# Proiect_v23.net
KiCad netlist of a schematic drawn in EAGLE
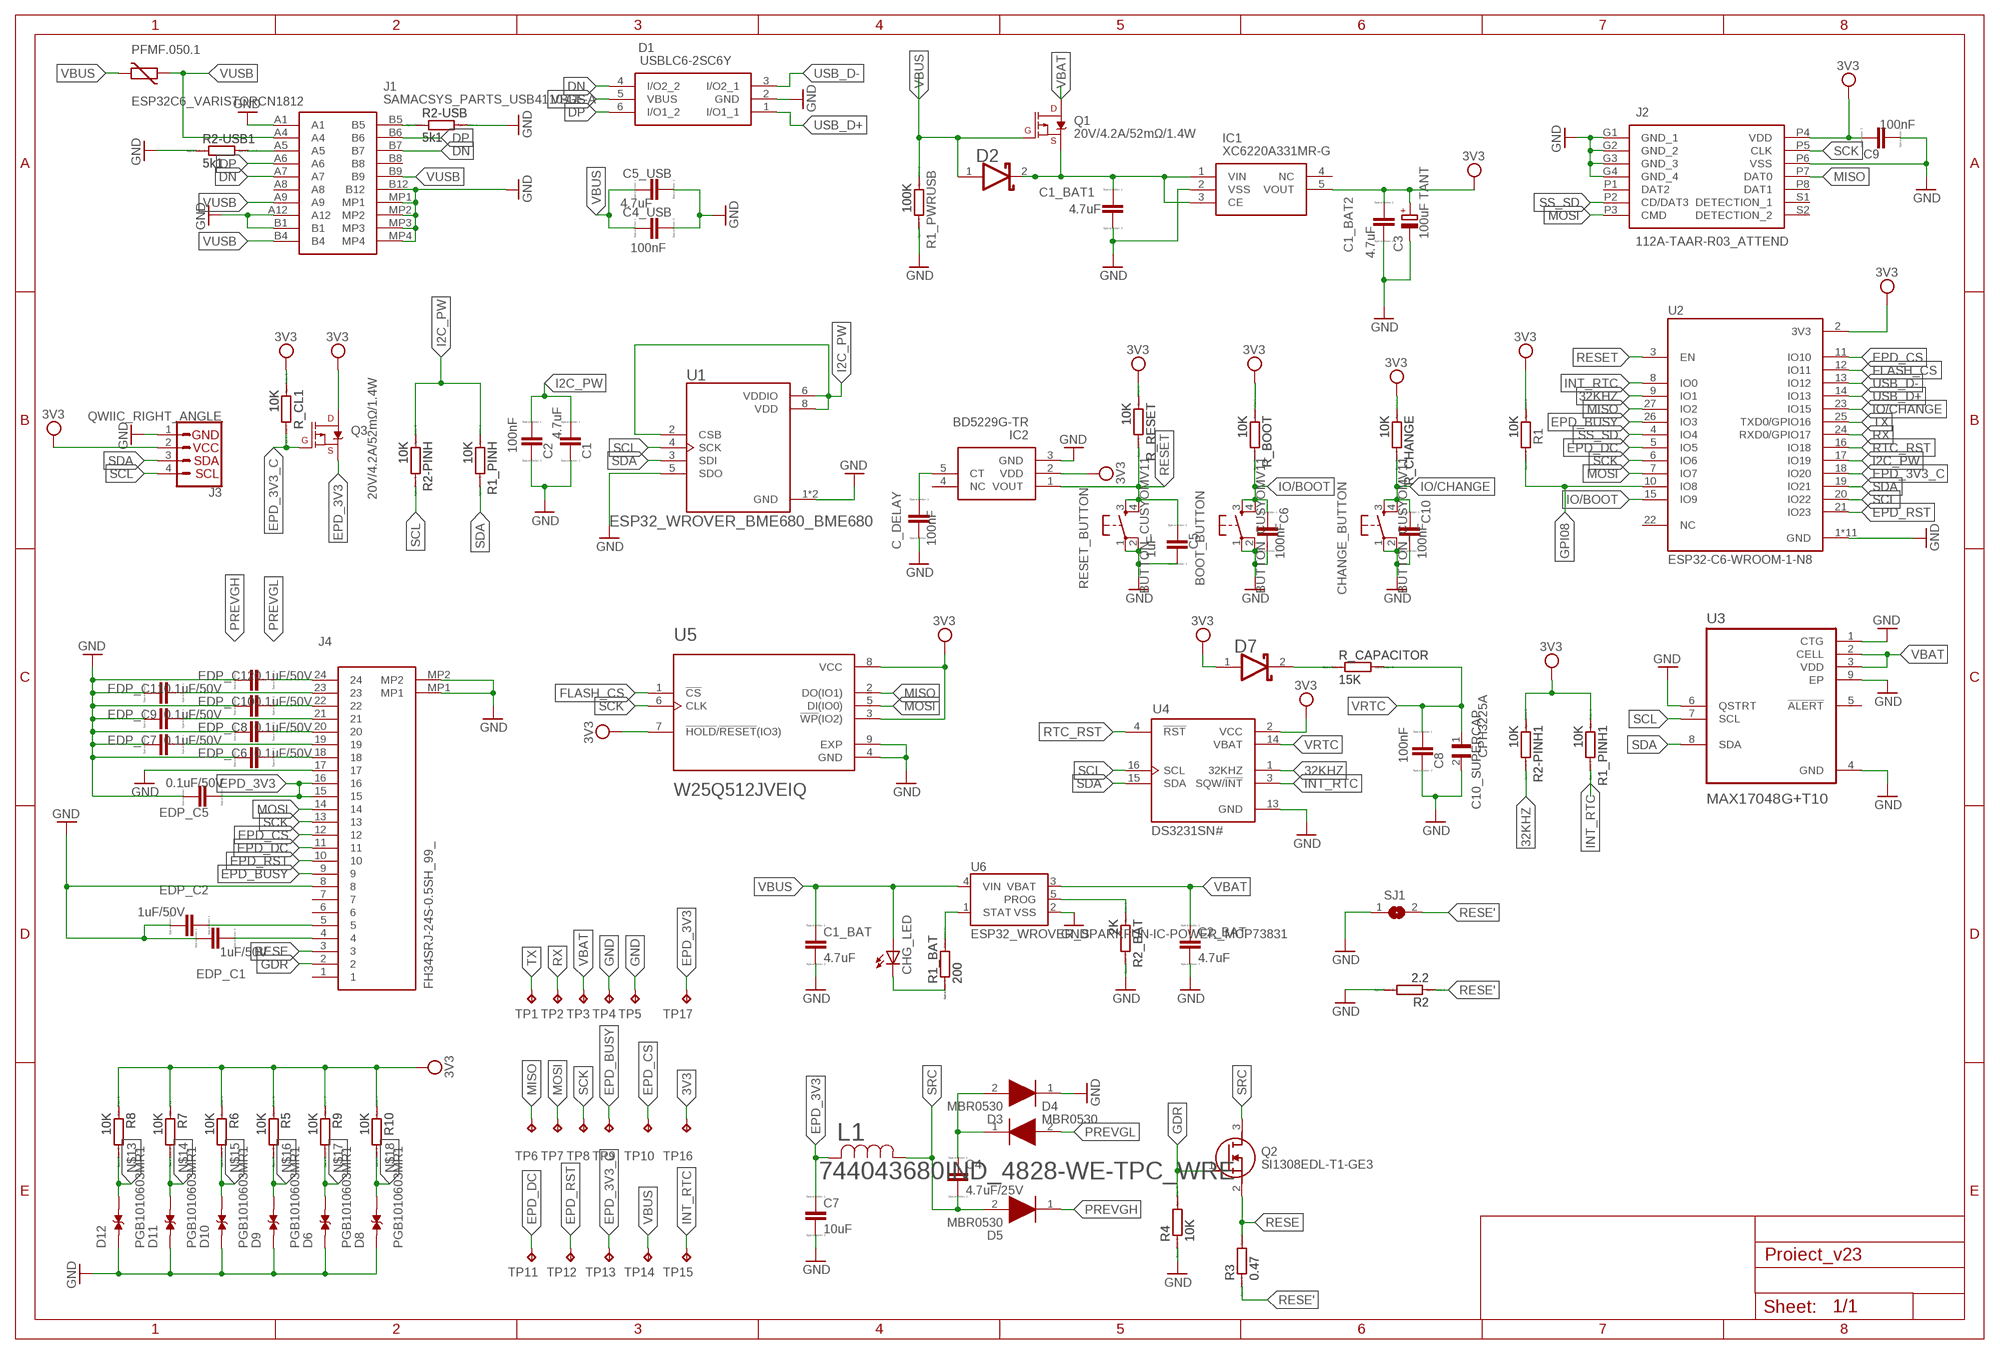
[diagram p0: schematic, sheet 1]

(export (version "E")
  (design (tool "Eeschema 10.0.6"))
  (components
    (comp (ref "BOOT_BUTTON")
      (value "BUTTON_CUSYOMV11")
      (footprint "eagle-import:MYBUTTON")
      (libsource (lib "eagle-import") (part "BUTTON_CUSYOMV11"))
    )
    (comp (ref "C1")
      (value "4.7uF")
      (footprint "eagle-import:ESP32_WROVER_EAGLE-LTSPICE_C0402")
      (libsource (lib "eagle-import") (part "EAGLE-LTSPICE_C"))
    )
    (comp (ref "C1_BAT")
      (value "4.7uF")
      (footprint "eagle-import:ESP32_WROVER_EAGLE-LTSPICE_C0402")
      (libsource (lib "eagle-import") (part "ESP32_WROVER_EAGLE-LTSPICE_CC0402"))
    )
    (comp (ref "C1_BAT1")
      (value "4.7uF")
      (footprint "eagle-import:ESP32_WROVER_EAGLE-LTSPICE_C0402")
      (libsource (lib "eagle-import") (part "EAGLE-LTSPICE_C"))
    )
    (comp (ref "C1_BAT2")
      (value "4.7uF")
      (footprint "eagle-import:ESP32_WROVER_EAGLE-LTSPICE_C0402")
      (libsource (lib "eagle-import") (part "EAGLE-LTSPICE_C"))
    )
    (comp (ref "C2")
      (value "100nF")
      (footprint "eagle-import:ESP32_WROVER_EAGLE-LTSPICE_C0402")
      (libsource (lib "eagle-import") (part "EAGLE-LTSPICE_C"))
    )
    (comp (ref "C2_BAT")
      (value "4.7uF")
      (footprint "eagle-import:ESP32_WROVER_EAGLE-LTSPICE_C0402")
      (libsource (lib "eagle-import") (part "ESP32_WROVER_EAGLE-LTSPICE_CC0402"))
    )
    (comp (ref "C3")
      (value "100uF TANT")
      (footprint "eagle-import:RCL_CT3528")
      (libsource (lib "eagle-import") (part "RCL_CPOL-EUCT3528"))
    )
    (comp (ref "C4")
      (value "4.7uF/25V")
      (footprint "eagle-import:ESP32_WROVER_EAGLE-LTSPICE_C0402")
      (libsource (lib "eagle-import") (part "ESP32_WROVER_EAGLE-LTSPICE_CC0402"))
    )
    (comp (ref "C4_USB")
      (value "100nF")
      (footprint "eagle-import:ESP32_WROVER_EAGLE-LTSPICE_C0402")
      (libsource (lib "eagle-import") (part "EAGLE-LTSPICE_C"))
    )
    (comp (ref "C5")
      (value "1uF")
      (footprint "eagle-import:ESP32_WROVER_EAGLE-LTSPICE_C0402")
      (libsource (lib "eagle-import") (part "EAGLE-LTSPICE_C"))
    )
    (comp (ref "C5_USB")
      (value "4.7uF")
      (footprint "eagle-import:ESP32_WROVER_EAGLE-LTSPICE_C0402")
      (libsource (lib "eagle-import") (part "EAGLE-LTSPICE_C"))
    )
    (comp (ref "C6")
      (value "100nF")
      (footprint "eagle-import:ESP32_WROVER_EAGLE-LTSPICE_C0402")
      (libsource (lib "eagle-import") (part "EAGLE-LTSPICE_C"))
    )
    (comp (ref "C7")
      (value "10uF")
      (footprint "eagle-import:ESP32_WROVER_EAGLE-LTSPICE_C0402")
      (libsource (lib "eagle-import") (part "ESP32_WROVER_EAGLE-LTSPICE_CC0402"))
    )
    (comp (ref "C8")
      (value "100nF")
      (footprint "eagle-import:ESP32_WROVER_EAGLE-LTSPICE_C0402")
      (libsource (lib "eagle-import") (part "EAGLE-LTSPICE_C"))
    )
    (comp (ref "C9")
      (value "100nF")
      (footprint "eagle-import:ESP32_WROVER_EAGLE-LTSPICE_C0402")
      (libsource (lib "eagle-import") (part "EAGLE-LTSPICE_C"))
    )
    (comp (ref "C10")
      (value "100nF")
      (footprint "eagle-import:ESP32_WROVER_EAGLE-LTSPICE_C0402")
      (libsource (lib "eagle-import") (part "EAGLE-LTSPICE_C"))
    )
    (comp (ref "C10_SUPERCAP")
      (value "CPH3225A")
      (footprint "eagle-import:CAPCP3225X100N")
      (fields (field (name "MF") "Seiko Instruments"))
      (libsource (lib "eagle-import") (part "CPH3225A"))
    )
    (comp (ref "CHANGE_BUTTON")
      (value "BUTTON_CUSYOMV11")
      (footprint "eagle-import:MYBUTTON")
      (libsource (lib "eagle-import") (part "BUTTON_CUSYOMV11"))
    )
    (comp (ref "CHG_LED")
      (value "ADAFRUIT_LEDCHIP-LED0603")
      (footprint "eagle-import:ADAFRUIT_CHIP-LED0603")
      (libsource (lib "eagle-import") (part "ADAFRUIT_LEDCHIP-LED0603"))
    )
    (comp (ref "C_DELAY")
      (value "100nF")
      (footprint "eagle-import:ESP32_WROVER_EAGLE-LTSPICE_C0402")
      (libsource (lib "eagle-import") (part "EAGLE-LTSPICE_C"))
    )
    (comp (ref "D1")
      (value "USBLC6-2SC6Y")
      (footprint "eagle-import:SOT95P280X145-6N")
      (fields (field (name "MF") "STMicroelectronics"))
      (libsource (lib "eagle-import") (part "USBLC6-2SC6Y"))
    )
    (comp (ref "D2")
      (value "ESP32_WROVER_AVX---SD0805S020S1R0_AVX_SD0805S020S1R0_0_0")
      (footprint "eagle-import:ESP32_WROVER_AVX---SD0805S020S1R0_AVX_SD0805S020S1R0_0")
      (libsource (lib "eagle-import") (part "ESP32_WROVER_AVX---SD0805S020S1R0_AVX_SD0805S020S1R0_0_0"))
    )
    (comp (ref "D3")
      (value "MBR0530")
      (footprint "eagle-import:SOD3716X135N")
      (fields (field (name "MF") "ON Semiconductor"))
      (libsource (lib "eagle-import") (part "MBR0530"))
    )
    (comp (ref "D4")
      (value "MBR0530")
      (footprint "eagle-import:SOD3716X135N")
      (fields (field (name "MF") "ON Semiconductor"))
      (libsource (lib "eagle-import") (part "MBR0530"))
    )
    (comp (ref "D5")
      (value "MBR0530")
      (footprint "eagle-import:SOD3716X135N")
      (fields (field (name "MF") "ON Semiconductor"))
      (libsource (lib "eagle-import") (part "MBR0530"))
    )
    (comp (ref "D6")
      (value "PGB1010603MR1")
      (footprint "eagle-import:DIOC1608X36N")
      (libsource (lib "eagle-import") (part "PGB1010603MR1"))
    )
    (comp (ref "D7")
      (value "ESP32_WROVER_AVX---SD0805S020S1R0_AVX_SD0805S020S1R0_0_0")
      (footprint "eagle-import:ESP32_WROVER_AVX---SD0805S020S1R0_AVX_SD0805S020S1R0_0")
      (libsource (lib "eagle-import") (part "ESP32_WROVER_AVX---SD0805S020S1R0_AVX_SD0805S020S1R0_0_0"))
    )
    (comp (ref "D8")
      (value "PGB1010603MR1")
      (footprint "eagle-import:DIOC1608X36N")
      (libsource (lib "eagle-import") (part "PGB1010603MR1"))
    )
    (comp (ref "D9")
      (value "PGB1010603MR1")
      (footprint "eagle-import:DIOC1608X36N")
      (libsource (lib "eagle-import") (part "PGB1010603MR1"))
    )
    (comp (ref "D10")
      (value "PGB1010603MR1")
      (footprint "eagle-import:DIOC1608X36N")
      (libsource (lib "eagle-import") (part "PGB1010603MR1"))
    )
    (comp (ref "D11")
      (value "PGB1010603MR1")
      (footprint "eagle-import:DIOC1608X36N")
      (libsource (lib "eagle-import") (part "PGB1010603MR1"))
    )
    (comp (ref "D12")
      (value "PGB1010603MR1")
      (footprint "eagle-import:DIOC1608X36N")
      (libsource (lib "eagle-import") (part "PGB1010603MR1"))
    )
    (comp (ref "EDP_C1")
      (value "1uF/50V")
      (footprint "eagle-import:ESP32_WROVER_EAGLE-LTSPICE_C0402")
      (libsource (lib "eagle-import") (part "EAGLE-LTSPICE_C"))
    )
    (comp (ref "EDP_C2")
      (value "1uF/50V")
      (footprint "eagle-import:ESP32_WROVER_EAGLE-LTSPICE_C0402")
      (libsource (lib "eagle-import") (part "EAGLE-LTSPICE_C"))
    )
    (comp (ref "EDP_C5")
      (value "0.1uF/50V")
      (footprint "eagle-import:ESP32_WROVER_EAGLE-LTSPICE_C0402")
      (libsource (lib "eagle-import") (part "EAGLE-LTSPICE_C"))
    )
    (comp (ref "EDP_C6")
      (value "0.1uF/50V")
      (footprint "eagle-import:ESP32_WROVER_EAGLE-LTSPICE_C0402")
      (libsource (lib "eagle-import") (part "EAGLE-LTSPICE_C"))
    )
    (comp (ref "EDP_C7")
      (value "0.1uF/50V")
      (footprint "eagle-import:ESP32_WROVER_EAGLE-LTSPICE_C0402")
      (libsource (lib "eagle-import") (part "EAGLE-LTSPICE_C"))
    )
    (comp (ref "EDP_C8")
      (value "0.1uF/50V")
      (footprint "eagle-import:ESP32_WROVER_EAGLE-LTSPICE_C0402")
      (libsource (lib "eagle-import") (part "EAGLE-LTSPICE_C"))
    )
    (comp (ref "EDP_C9")
      (value "0.1uF/50V")
      (footprint "eagle-import:ESP32_WROVER_EAGLE-LTSPICE_C0402")
      (libsource (lib "eagle-import") (part "EAGLE-LTSPICE_C"))
    )
    (comp (ref "EDP_C10")
      (value "0.1uF/50V")
      (footprint "eagle-import:ESP32_WROVER_EAGLE-LTSPICE_C0402")
      (libsource (lib "eagle-import") (part "EAGLE-LTSPICE_C"))
    )
    (comp (ref "EDP_C11")
      (value "0.1uF/50V")
      (footprint "eagle-import:ESP32_WROVER_EAGLE-LTSPICE_C0402")
      (libsource (lib "eagle-import") (part "EAGLE-LTSPICE_C"))
    )
    (comp (ref "EDP_C12")
      (value "0.1uF/50V")
      (footprint "eagle-import:ESP32_WROVER_EAGLE-LTSPICE_C0402")
      (libsource (lib "eagle-import") (part "EAGLE-LTSPICE_C"))
    )
    (comp (ref "IC1")
      (value "XC6220A331MR-G")
      (footprint "eagle-import:SOT95P280X120-5N")
      (fields (field (name "MOUSER_PART_NUMBER") "865-XC6220A331MR-G"))
      (libsource (lib "eagle-import") (part "XC6220A331MR-G"))
    )
    (comp (ref "IC2")
      (value "BD5229G-TR")
      (footprint "eagle-import:SOT95P280X125-5N")
      (fields (field (name "MOUSER_PART_NUMBER") "755-BD5229G-TR"))
      (libsource (lib "eagle-import") (part "BD5229G-TR"))
    )
    (comp (ref "J1")
      (value "SAMACSYS_PARTS_USB4110-GF-A")
      (footprint "eagle-import:SAMACSYS_PARTS_USB4110GFA")
      (fields
        (field (name "MANUFACTURER_PART_NUMBER") "USB4110-GF-A")
        (field (name "MOUSER_PART_NUMBER") "640-USB4110-GF-A")
      )
      (libsource (lib "eagle-import") (part "SAMACSYS_PARTS_USB4110-GF-A"))
    )
    (comp (ref "J2")
      (value "112A-TAAR-R03_ATTEND")
      (footprint "eagle-import:112ATAARR03ATTEND")
      (fields (field (name "MANUFACTURER_PART_NUMBER") "112A-TAAR-R03 ATTEND"))
      (libsource (lib "eagle-import") (part "112A-TAAR-R03_ATTEND"))
    )
    (comp (ref "J3")
      (value "QWIIC_RIGHT_ANGLE")
      (footprint "eagle-import:JST04_1MM_RA")
      (libsource (lib "eagle-import") (part "QWIIC_CONNECTORJS-1MM"))
    )
    (comp (ref "J4")
      (value "FH34SRJ-24S-0.5SH_99_")
      (footprint "eagle-import:FH34SRJ24S05SH99")
      (fields
        (field (name "MANUFACTURER_PART_NUMBER") "FH34SRJ-24S-0.5SH(99)")
        (field (name "MOUSER_PART_NUMBER") "798-FH34SRJ24S05SH99")
      )
      (libsource (lib "eagle-import") (part "FH34SRJ-24S-0.5SH_99_"))
    )
    (comp (ref "L1")
      (value "744043680IND_4828-WE-TPC_WRE")
      (footprint "eagle-import:IND_4828-WE-TPC_WRE")
      (fields
        (field (name "MANUFACTURER_PART_NUMBER") "744043680")
        (field (name "COPYRIGHT") "Copyright (C) 2024 Ultra Librarian. All rights reserved.")
      )
      (libsource (lib "eagle-import") (part "744043680IND_4828-WE-TPC_WRE"))
    )
    (comp (ref "PFMF.050.1")
      (value "ESP32C6_VARISTORCN1812")
      (footprint "eagle-import:ESP32C6_VARISTOR_CT_CN1812")
      (libsource (lib "eagle-import") (part "ESP32C6_VARISTORCN1812"))
    )
    (comp (ref "Q1")
      (value "20V/4.2A/52mΩ/1.4W")
      (footprint "eagle-import:ESP32_WROVER_SPARKFUN-DISCRETESEMI_SOT23-3")
      (libsource (lib "eagle-import") (part "ESP32_WROVER_SPARKFUN-DISCRETESEMI_MOSFET_PCH-DMG2305UX-7"))
    )
    (comp (ref "Q2")
      (value "SI1308EDL-T1-GE3")
      (footprint "eagle-import:SOT65P210X110-3N")
      (fields (field (name "MF") "Vishay Siliconix"))
      (libsource (lib "eagle-import") (part "SI1308EDL-T1-GE3"))
    )
    (comp (ref "Q3")
      (value "20V/4.2A/52mΩ/1.4W")
      (footprint "eagle-import:ESP32_WROVER_SPARKFUN-DISCRETESEMI_SOT23-3")
      (libsource (lib "eagle-import") (part "ESP32_WROVER_SPARKFUN-DISCRETESEMI_MOSFET_PCH-DMG2305UX-7"))
    )
    (comp (ref "R1")
      (value "10K")
      (footprint "eagle-import:ESP32_WROVER_EAGLE-LTSPICE_R0402")
      (libsource (lib "eagle-import") (part "ESP32_WROVER_EAGLE-LTSPICE_R"))
    )
    (comp (ref "R1_BAT")
      (value "200")
      (footprint "eagle-import:ESP32_WROVER_EAGLE-LTSPICE_R0402")
      (libsource (lib "eagle-import") (part "ESP32_WROVER_EAGLE-LTSPICE_R"))
    )
    (comp (ref "R1_PINH")
      (value "10K")
      (footprint "eagle-import:ESP32_WROVER_EAGLE-LTSPICE_R0402")
      (libsource (lib "eagle-import") (part "ESP32_WROVER_EAGLE-LTSPICE_R"))
    )
    (comp (ref "R1_PINH1")
      (value "10K")
      (footprint "eagle-import:ESP32_WROVER_EAGLE-LTSPICE_R0402")
      (libsource (lib "eagle-import") (part "ESP32_WROVER_EAGLE-LTSPICE_R"))
    )
    (comp (ref "R1_PWRUSB")
      (value "100K")
      (footprint "eagle-import:ESP32_WROVER_EAGLE-LTSPICE_R0402")
      (libsource (lib "eagle-import") (part "ESP32_WROVER_EAGLE-LTSPICE_R"))
    )
    (comp (ref "R2")
      (value "2.2")
      (footprint "eagle-import:ESP32_WROVER_EAGLE-LTSPICE_R0402")
      (libsource (lib "eagle-import") (part "ESP32_WROVER_EAGLE-LTSPICE_R"))
    )
    (comp (ref "R2-PINH")
      (value "10K")
      (footprint "eagle-import:ESP32_WROVER_EAGLE-LTSPICE_R0402")
      (libsource (lib "eagle-import") (part "ESP32_WROVER_EAGLE-LTSPICE_R"))
    )
    (comp (ref "R2-PINH1")
      (value "10K")
      (footprint "eagle-import:ESP32_WROVER_EAGLE-LTSPICE_R0402")
      (libsource (lib "eagle-import") (part "ESP32_WROVER_EAGLE-LTSPICE_R"))
    )
    (comp (ref "R2-USB")
      (value "5k1")
      (footprint "eagle-import:ESP32_WROVER_EAGLE-LTSPICE_R0402")
      (libsource (lib "eagle-import") (part "ESP32_WROVER_EAGLE-LTSPICE_R"))
    )
    (comp (ref "R2-USB1")
      (value "5k1")
      (footprint "eagle-import:ESP32_WROVER_EAGLE-LTSPICE_R0402")
      (libsource (lib "eagle-import") (part "ESP32_WROVER_EAGLE-LTSPICE_R"))
    )
    (comp (ref "R2_BAT")
      (value "2K")
      (footprint "eagle-import:ESP32_WROVER_EAGLE-LTSPICE_R0402")
      (libsource (lib "eagle-import") (part "ESP32_WROVER_EAGLE-LTSPICE_R"))
    )
    (comp (ref "R3")
      (value "0.47")
      (footprint "eagle-import:ESP32_WROVER_EAGLE-LTSPICE_R0402")
      (libsource (lib "eagle-import") (part "ESP32_WROVER_EAGLE-LTSPICE_R"))
    )
    (comp (ref "R4")
      (value "10K")
      (footprint "eagle-import:ESP32_WROVER_EAGLE-LTSPICE_R0402")
      (libsource (lib "eagle-import") (part "ESP32_WROVER_EAGLE-LTSPICE_R"))
    )
    (comp (ref "R5")
      (value "10K")
      (footprint "eagle-import:ESP32_WROVER_EAGLE-LTSPICE_R0402")
      (libsource (lib "eagle-import") (part "ESP32_WROVER_EAGLE-LTSPICE_R"))
    )
    (comp (ref "R6")
      (value "10K")
      (footprint "eagle-import:ESP32_WROVER_EAGLE-LTSPICE_R0402")
      (libsource (lib "eagle-import") (part "ESP32_WROVER_EAGLE-LTSPICE_R"))
    )
    (comp (ref "R7")
      (value "10K")
      (footprint "eagle-import:ESP32_WROVER_EAGLE-LTSPICE_R0402")
      (libsource (lib "eagle-import") (part "ESP32_WROVER_EAGLE-LTSPICE_R"))
    )
    (comp (ref "R8")
      (value "10K")
      (footprint "eagle-import:ESP32_WROVER_EAGLE-LTSPICE_R0402")
      (libsource (lib "eagle-import") (part "ESP32_WROVER_EAGLE-LTSPICE_R"))
    )
    (comp (ref "R9")
      (value "10K")
      (footprint "eagle-import:ESP32_WROVER_EAGLE-LTSPICE_R0402")
      (libsource (lib "eagle-import") (part "ESP32_WROVER_EAGLE-LTSPICE_R"))
    )
    (comp (ref "R10")
      (value "10K")
      (footprint "eagle-import:ESP32_WROVER_EAGLE-LTSPICE_R0402")
      (libsource (lib "eagle-import") (part "ESP32_WROVER_EAGLE-LTSPICE_R"))
    )
    (comp (ref "RESET_BUTTON")
      (value "BUTTON_CUSYOMV11")
      (footprint "eagle-import:MYBUTTON")
      (libsource (lib "eagle-import") (part "BUTTON_CUSYOMV11"))
    )
    (comp (ref "R_BOOT")
      (value "10K")
      (footprint "eagle-import:ESP32_WROVER_EAGLE-LTSPICE_R0402")
      (libsource (lib "eagle-import") (part "ESP32_WROVER_EAGLE-LTSPICE_R"))
    )
    (comp (ref "R_CAPACITOR")
      (value "15K")
      (footprint "eagle-import:ESP32_WROVER_EAGLE-LTSPICE_R0402")
      (libsource (lib "eagle-import") (part "ESP32_WROVER_EAGLE-LTSPICE_R"))
    )
    (comp (ref "R_CHANGE")
      (value "10K")
      (footprint "eagle-import:ESP32_WROVER_EAGLE-LTSPICE_R0402")
      (libsource (lib "eagle-import") (part "ESP32_WROVER_EAGLE-LTSPICE_R"))
    )
    (comp (ref "R_CL1")
      (value "10K")
      (footprint "eagle-import:ESP32_WROVER_EAGLE-LTSPICE_R0402")
      (libsource (lib "eagle-import") (part "ESP32_WROVER_EAGLE-LTSPICE_R"))
    )
    (comp (ref "R_RESET")
      (value "10K")
      (footprint "eagle-import:ESP32_WROVER_EAGLE-LTSPICE_R0402")
      (libsource (lib "eagle-import") (part "ESP32_WROVER_EAGLE-LTSPICE_R"))
    )
    (comp (ref "SJ1") (value "SJ") (footprint "eagle-import:SJ") (libsource (lib "eagle-import") (part "SJ")))
    (comp (ref "TP1")
      (value "TP")
      (footprint "eagle-import:TP20R")
      (libsource (lib "eagle-import") (part "TP"))
    )
    (comp (ref "TP2")
      (value "TP")
      (footprint "eagle-import:TP20R")
      (libsource (lib "eagle-import") (part "TP"))
    )
    (comp (ref "TP3")
      (value "TP")
      (footprint "eagle-import:TP20R")
      (libsource (lib "eagle-import") (part "TP"))
    )
    (comp (ref "TP4")
      (value "TP")
      (footprint "eagle-import:TP20R")
      (libsource (lib "eagle-import") (part "TP"))
    )
    (comp (ref "TP5")
      (value "TP")
      (footprint "eagle-import:TP20R")
      (libsource (lib "eagle-import") (part "TP"))
    )
    (comp (ref "TP6")
      (value "TP")
      (footprint "eagle-import:TP20R")
      (libsource (lib "eagle-import") (part "TP"))
    )
    (comp (ref "TP7")
      (value "TP")
      (footprint "eagle-import:TP20R")
      (libsource (lib "eagle-import") (part "TP"))
    )
    (comp (ref "TP8")
      (value "TP")
      (footprint "eagle-import:TP20R")
      (libsource (lib "eagle-import") (part "TP"))
    )
    (comp (ref "TP9")
      (value "TP")
      (footprint "eagle-import:TP20R")
      (libsource (lib "eagle-import") (part "TP"))
    )
    (comp (ref "TP10")
      (value "TP")
      (footprint "eagle-import:TP20R")
      (libsource (lib "eagle-import") (part "TP"))
    )
    (comp (ref "TP11")
      (value "TP")
      (footprint "eagle-import:TP20R")
      (libsource (lib "eagle-import") (part "TP"))
    )
    (comp (ref "TP12")
      (value "TP")
      (footprint "eagle-import:TP20R")
      (libsource (lib "eagle-import") (part "TP"))
    )
    (comp (ref "TP13")
      (value "TP")
      (footprint "eagle-import:TP20R")
      (libsource (lib "eagle-import") (part "TP"))
    )
    (comp (ref "TP14")
      (value "TP")
      (footprint "eagle-import:TP20R")
      (libsource (lib "eagle-import") (part "TP"))
    )
    (comp (ref "TP15")
      (value "TP")
      (footprint "eagle-import:TP20R")
      (libsource (lib "eagle-import") (part "TP"))
    )
    (comp (ref "TP16")
      (value "TP")
      (footprint "eagle-import:TP20R")
      (libsource (lib "eagle-import") (part "TP"))
    )
    (comp (ref "TP17")
      (value "TP")
      (footprint "eagle-import:TP20R")
      (libsource (lib "eagle-import") (part "TP"))
    )
    (comp (ref "U1")
      (value "ESP32_WROVER_BME680_BME680")
      (footprint "eagle-import:ESP32_WROVER_BME680_PSON80P300X300X100-8N")
      (fields (field (name "MF") "Bosch Sensortec") (field (name "MP") "BME680"))
      (libsource (lib "eagle-import") (part "ESP32_WROVER_BME680_BME680"))
    )
    (comp (ref "U2")
      (value "ESP32-C6-WROOM-1-N8")
      (footprint "eagle-import:XCVR_ESP32-C6-WROOM-1-N8")
      (fields (field (name "MF") "Espressif Systems"))
      (libsource (lib "eagle-import") (part "ESP32-C6-WROOM-1-N8"))
    )
    (comp (ref "U3")
      (value "MAX17048G+T10")
      (footprint "eagle-import:SON50P200X200X80-9N")
      (fields (field (name "MF") "Analog Devices"))
      (libsource (lib "eagle-import") (part "MAX17048G+T10"))
    )
    (comp (ref "U4")
      (value "DS3231SN#")
      (footprint "eagle-import:SOIC127P1032X265-16N")
      (fields (field (name "MF") "Analog Devices"))
      (libsource (lib "eagle-import") (part "DS3231SN#"))
    )
    (comp (ref "U5")
      (value "W25Q512JVEIQ")
      (footprint "eagle-import:SON127P600X800X80-9N")
      (fields (field (name "MF") "Winbond Electronics"))
      (libsource (lib "eagle-import") (part "W25Q512JVEIQ"))
    )
    (comp (ref "U6")
      (value "ESP32_WROVER_SPARKFUN-IC-POWER_MCP73831")
      (footprint "eagle-import:ESP32_WROVER_SPARKFUN-IC-POWER_SOT23-5")
      (libsource (lib "eagle-import") (part "ESP32_WROVER_SPARKFUN-IC-POWER_MCP73831"))
    )
  )
  (nets
    (net (code "1") (name "3V3") (class "Default")
      (node (ref "C1_BAT2") (pin "1") (pinfunction "1_1") (pintype "passive"))
      (node (ref "C3") (pin "+") (pinfunction "+_+") (pintype "passive"))
      (node (ref "C9") (pin "2") (pinfunction "2_2") (pintype "passive"))
      (node (ref "D7") (pin "1") (pinfunction "ANODE_1") (pintype "bidirectional"))
      (node (ref "IC1") (pin "5") (pinfunction "VOUT_5") (pintype "bidirectional"))
      (node (ref "IC2") (pin "2") (pinfunction "VDD_2") (pintype "bidirectional"))
      (node (ref "J2") (pin "P4") (pinfunction "VDD_P4") (pintype "bidirectional"))
      (node (ref "J3") (pin "2") (pinfunction "2_2") (pintype "power_in"))
      (node (ref "Q3") (pin "3") (pinfunction "D_3") (pintype "bidirectional"))
      (node (ref "R1") (pin "1") (pinfunction "1_1") (pintype "passive"))
      (node (ref "R10") (pin "1") (pinfunction "1_1") (pintype "passive"))
      (node (ref "R1_PINH1") (pin "1") (pinfunction "1_1") (pintype "passive"))
      (node (ref "R2-PINH1") (pin "1") (pinfunction "1_1") (pintype "passive"))
      (node (ref "R5") (pin "1") (pinfunction "1_1") (pintype "passive"))
      (node (ref "R6") (pin "1") (pinfunction "1_1") (pintype "passive"))
      (node (ref "R7") (pin "1") (pinfunction "1_1") (pintype "passive"))
      (node (ref "R8") (pin "1") (pinfunction "1_1") (pintype "passive"))
      (node (ref "R9") (pin "1") (pinfunction "1_1") (pintype "passive"))
      (node (ref "R_BOOT") (pin "1") (pinfunction "1_1") (pintype "passive"))
      (node (ref "R_CHANGE") (pin "1") (pinfunction "1_1") (pintype "passive"))
      (node (ref "R_CL1") (pin "1") (pinfunction "1_1") (pintype "passive"))
      (node (ref "R_RESET") (pin "1") (pinfunction "1_1") (pintype "passive"))
      (node (ref "TP16") (pin "TP") (pinfunction "TP_TP") (pintype "input"))
      (node (ref "U2") (pin "2") (pinfunction "3V3_2") (pintype "power_in"))
      (node (ref "U4") (pin "2") (pinfunction "VCC_2") (pintype "power_in"))
      (node (ref "U5") (pin "3") (pinfunction "~{WP}(IO2)_3") (pintype "bidirectional"))
      (node (ref "U5") (pin "7") (pinfunction "~{HOLD}/~{RESET}(IO3)_7") (pintype "bidirectional"))
      (node (ref "U5") (pin "8") (pinfunction "VCC_8") (pintype "power_in"))
    )
    (net (code "2") (name "32KHZ") (class "Default")
      (node (ref "R2-PINH1") (pin "2") (pinfunction "2_2") (pintype "passive"))
      (node (ref "U2") (pin "9") (pinfunction "IO1_9") (pintype "bidirectional"))
      (node (ref "U4") (pin "1") (pinfunction "32KHZ_1") (pintype "output"))
    )
    (net (code "3") (name "DN") (class "Default")
      (node (ref "D1") (pin "4") (pinfunction "I/O2_2_4") (pintype "bidirectional"))
      (node (ref "J1") (pin "A7") (pinfunction "A7_A7") (pintype "bidirectional"))
      (node (ref "J1") (pin "B7") (pinfunction "B7_B7") (pintype "bidirectional"))
    )
    (net (code "4") (name "DP") (class "Default")
      (node (ref "D1") (pin "6") (pinfunction "I/O1_2_6") (pintype "bidirectional"))
      (node (ref "J1") (pin "A6") (pinfunction "A6_A6") (pintype "bidirectional"))
      (node (ref "J1") (pin "B6") (pinfunction "B6_B6") (pintype "bidirectional"))
    )
    (net (code "5") (name "EPD_3V3") (class "Default")
      (node (ref "C7") (pin "1") (pinfunction "1_1") (pintype "passive"))
      (node (ref "EDP_C5") (pin "1") (pinfunction "1_1") (pintype "passive"))
      (node (ref "J4") (pin "15") (pinfunction "15_15") (pintype "bidirectional"))
      (node (ref "J4") (pin "16") (pinfunction "16_16") (pintype "bidirectional"))
      (node (ref "L1") (pin "2") (pinfunction "2_2") (pintype "passive"))
      (node (ref "Q3") (pin "2") (pinfunction "S_2") (pintype "bidirectional"))
      (node (ref "TP17") (pin "TP") (pinfunction "TP_TP") (pintype "input"))
    )
    (net (code "6") (name "EPD_3V3_C") (class "Default")
      (node (ref "Q3") (pin "1") (pinfunction "G_1") (pintype "bidirectional"))
      (node (ref "R_CL1") (pin "2") (pinfunction "2_2") (pintype "passive"))
      (node (ref "TP13") (pin "TP") (pinfunction "TP_TP") (pintype "input"))
      (node (ref "U2") (pin "18") (pinfunction "IO20_18") (pintype "bidirectional"))
    )
    (net (code "7") (name "EPD_BUSY") (class "Default")
      (node (ref "J4") (pin "9") (pinfunction "9_9") (pintype "bidirectional"))
      (node (ref "TP9") (pin "TP") (pinfunction "TP_TP") (pintype "input"))
      (node (ref "U2") (pin "26") (pinfunction "IO3_26") (pintype "bidirectional"))
    )
    (net (code "8") (name "EPD_CS") (class "Default")
      (node (ref "J4") (pin "12") (pinfunction "12_12") (pintype "bidirectional"))
      (node (ref "TP10") (pin "TP") (pinfunction "TP_TP") (pintype "input"))
      (node (ref "U2") (pin "11") (pinfunction "IO10_11") (pintype "bidirectional"))
    )
    (net (code "9") (name "EPD_DC") (class "Default")
      (node (ref "J4") (pin "11") (pinfunction "11_11") (pintype "bidirectional"))
      (node (ref "TP11") (pin "TP") (pinfunction "TP_TP") (pintype "input"))
      (node (ref "U2") (pin "5") (pinfunction "IO5_5") (pintype "bidirectional"))
    )
    (net (code "10") (name "EPD_RST") (class "Default")
      (node (ref "J4") (pin "10") (pinfunction "10_10") (pintype "bidirectional"))
      (node (ref "TP12") (pin "TP") (pinfunction "TP_TP") (pintype "input"))
      (node (ref "U2") (pin "21") (pinfunction "IO23_21") (pintype "bidirectional"))
    )
    (net (code "11") (name "FLASH_CS") (class "Default")
      (node (ref "U2") (pin "12") (pinfunction "IO11_12") (pintype "bidirectional"))
      (node (ref "U5") (pin "1") (pinfunction "~{CS}_1") (pintype "input"))
    )
    (net (code "12") (name "GDR") (class "Default")
      (node (ref "J4") (pin "2") (pinfunction "2_2") (pintype "bidirectional"))
      (node (ref "Q2") (pin "1") (pinfunction "G_1") (pintype "bidirectional"))
      (node (ref "R4") (pin "2") (pinfunction "2_2") (pintype "passive"))
    )
    (net (code "13") (name "GND") (class "Default")
      (node (ref "BOOT_BUTTON") (pin "1") (pinfunction "1_1") (pintype "passive"))
      (node (ref "BOOT_BUTTON") (pin "2") (pinfunction "2_2") (pintype "passive"))
      (node (ref "C1") (pin "2") (pinfunction "2_2") (pintype "passive"))
      (node (ref "C10") (pin "2") (pinfunction "2_2") (pintype "passive"))
      (node (ref "C10_SUPERCAP") (pin "2") (pinfunction "2_2") (pintype "passive"))
      (node (ref "C1_BAT") (pin "2") (pinfunction "2_2") (pintype "passive"))
      (node (ref "C1_BAT1") (pin "2") (pinfunction "2_2") (pintype "passive"))
      (node (ref "C1_BAT2") (pin "2") (pinfunction "2_2") (pintype "passive"))
      (node (ref "C2") (pin "2") (pinfunction "2_2") (pintype "passive"))
      (node (ref "C2_BAT") (pin "2") (pinfunction "2_2") (pintype "passive"))
      (node (ref "C3") (pin "-") (pinfunction "-_-") (pintype "passive"))
      (node (ref "C4_USB") (pin "2") (pinfunction "2_2") (pintype "passive"))
      (node (ref "C5") (pin "2") (pinfunction "2_2") (pintype "passive"))
      (node (ref "C5_USB") (pin "2") (pinfunction "2_2") (pintype "passive"))
      (node (ref "C6") (pin "2") (pinfunction "2_2") (pintype "passive"))
      (node (ref "C7") (pin "2") (pinfunction "2_2") (pintype "passive"))
      (node (ref "C8") (pin "2") (pinfunction "2_2") (pintype "passive"))
      (node (ref "C9") (pin "1") (pinfunction "1_1") (pintype "passive"))
      (node (ref "CHANGE_BUTTON") (pin "1") (pinfunction "1_1") (pintype "passive"))
      (node (ref "CHANGE_BUTTON") (pin "2") (pinfunction "2_2") (pintype "passive"))
      (node (ref "C_DELAY") (pin "2") (pinfunction "2_2") (pintype "passive"))
      (node (ref "D1") (pin "2") (pinfunction "GND_2") (pintype "bidirectional"))
      (node (ref "D10") (pin "1") (pinfunction "1_1") (pintype "passive"))
      (node (ref "D11") (pin "1") (pinfunction "1_1") (pintype "passive"))
      (node (ref "D12") (pin "1") (pinfunction "1_1") (pintype "passive"))
      (node (ref "D3") (pin "1") (pinfunction "K_1") (pintype "bidirectional"))
      (node (ref "D6") (pin "1") (pinfunction "1_1") (pintype "passive"))
      (node (ref "D8") (pin "1") (pinfunction "1_1") (pintype "passive"))
      (node (ref "D9") (pin "1") (pinfunction "1_1") (pintype "passive"))
      (node (ref "EDP_C1") (pin "1") (pinfunction "1_1") (pintype "passive"))
      (node (ref "EDP_C10") (pin "2") (pinfunction "2_2") (pintype "passive"))
      (node (ref "EDP_C11") (pin "2") (pinfunction "2_2") (pintype "passive"))
      (node (ref "EDP_C12") (pin "2") (pinfunction "2_2") (pintype "passive"))
      (node (ref "EDP_C2") (pin "2") (pinfunction "2_2") (pintype "passive"))
      (node (ref "EDP_C5") (pin "2") (pinfunction "2_2") (pintype "passive"))
      (node (ref "EDP_C6") (pin "2") (pinfunction "2_2") (pintype "passive"))
      (node (ref "EDP_C7") (pin "2") (pinfunction "2_2") (pintype "passive"))
      (node (ref "EDP_C8") (pin "2") (pinfunction "2_2") (pintype "passive"))
      (node (ref "EDP_C9") (pin "2") (pinfunction "2_2") (pintype "passive"))
      (node (ref "IC1") (pin "2") (pinfunction "VSS_2") (pintype "bidirectional"))
      (node (ref "IC2") (pin "3") (pinfunction "GND_3") (pintype "bidirectional"))
      (node (ref "J1") (pin "A1") (pinfunction "A1_A1") (pintype "bidirectional"))
      (node (ref "J1") (pin "A12") (pinfunction "A12_A12") (pintype "bidirectional"))
      (node (ref "J1") (pin "B1") (pinfunction "B1_B1") (pintype "bidirectional"))
      (node (ref "J1") (pin "B12") (pinfunction "B12_B12") (pintype "bidirectional"))
      (node (ref "J1") (pin "MP1") (pinfunction "MP1_MP1") (pintype "bidirectional"))
      (node (ref "J1") (pin "MP2") (pinfunction "MP2_MP2") (pintype "bidirectional"))
      (node (ref "J1") (pin "MP3") (pinfunction "MP3_MP3") (pintype "bidirectional"))
      (node (ref "J1") (pin "MP4") (pinfunction "MP4_MP4") (pintype "bidirectional"))
      (node (ref "J2") (pin "G1") (pinfunction "GND_1_G1") (pintype "bidirectional"))
      (node (ref "J2") (pin "G2") (pinfunction "GND_2_G2") (pintype "bidirectional"))
      (node (ref "J2") (pin "G3") (pinfunction "GND_3_G3") (pintype "bidirectional"))
      (node (ref "J2") (pin "G4") (pinfunction "GND_4_G4") (pintype "bidirectional"))
      (node (ref "J2") (pin "P6") (pinfunction "VSS_P6") (pintype "bidirectional"))
      (node (ref "J3") (pin "1") (pinfunction "1_1") (pintype "power_in"))
      (node (ref "J4") (pin "17") (pinfunction "17_17") (pintype "bidirectional"))
      (node (ref "J4") (pin "8") (pinfunction "8_8") (pintype "bidirectional"))
      (node (ref "J4") (pin "MP1") (pinfunction "MP1_MP1") (pintype "bidirectional"))
      (node (ref "J4") (pin "MP2") (pinfunction "MP2_MP2") (pintype "bidirectional"))
      (node (ref "R1_PWRUSB") (pin "2") (pinfunction "2_2") (pintype "passive"))
      (node (ref "R2") (pin "2") (pinfunction "2_2") (pintype "passive"))
      (node (ref "R2-USB") (pin "2") (pinfunction "2_2") (pintype "passive"))
      (node (ref "R2-USB1") (pin "1") (pinfunction "1_1") (pintype "passive"))
      (node (ref "R2_BAT") (pin "2") (pinfunction "2_2") (pintype "passive"))
      (node (ref "R4") (pin "1") (pinfunction "1_1") (pintype "passive"))
      (node (ref "RESET_BUTTON") (pin "1") (pinfunction "1_1") (pintype "passive"))
      (node (ref "RESET_BUTTON") (pin "2") (pinfunction "2_2") (pintype "passive"))
      (node (ref "SJ1") (pin "1") (pinfunction "1_1") (pintype "passive"))
      (node (ref "TP4") (pin "TP") (pinfunction "TP_TP") (pintype "input"))
      (node (ref "TP5") (pin "TP") (pinfunction "TP_TP") (pintype "input"))
      (node (ref "U1") (pin "1") (pinfunction "GND_1") (pintype "power_in"))
      (node (ref "U1") (pin "5") (pinfunction "SDO_5") (pintype "bidirectional"))
      (node (ref "U1") (pin "7") (pinfunction "GND_7") (pintype "power_in"))
      (node (ref "U2") (pin "1") (pinfunction "GND_1") (pintype "power_in"))
      (node (ref "U2") (pin "28") (pinfunction "GND_28") (pintype "power_in"))
      (node (ref "U2") (pin "29_1") (pinfunction "GND_29_1") (pintype "power_in"))
      (node (ref "U2") (pin "29_2") (pinfunction "GND_29_2") (pintype "power_in"))
      (node (ref "U2") (pin "29_3") (pinfunction "GND_29_3") (pintype "power_in"))
      (node (ref "U2") (pin "29_4") (pinfunction "GND_29_4") (pintype "power_in"))
      (node (ref "U2") (pin "29_5") (pinfunction "GND_29_5") (pintype "power_in"))
      (node (ref "U2") (pin "29_6") (pinfunction "GND_29_6") (pintype "power_in"))
      (node (ref "U2") (pin "29_7") (pinfunction "GND_29_7") (pintype "power_in"))
      (node (ref "U2") (pin "29_8") (pinfunction "GND_29_8") (pintype "power_in"))
      (node (ref "U2") (pin "29_9") (pinfunction "GND_29_9") (pintype "power_in"))
      (node (ref "U3") (pin "1") (pinfunction "CTG_1") (pintype "power_in"))
      (node (ref "U3") (pin "4") (pinfunction "GND_4") (pintype "power_in"))
      (node (ref "U3") (pin "6") (pinfunction "QSTRT_6") (pintype "input"))
      (node (ref "U3") (pin "9") (pinfunction "EP_9") (pintype "power_in"))
      (node (ref "U4") (pin "13") (pinfunction "GND_13") (pintype "power_in"))
      (node (ref "U5") (pin "4") (pinfunction "GND_4") (pintype "power_in"))
      (node (ref "U5") (pin "9") (pinfunction "EXP_9") (pintype "passive"))
      (node (ref "U6") (pin "2") (pinfunction "VSS_2") (pintype "power_in"))
    )
    (net (code "14") (name "GPI08") (class "Default")
      (node (ref "R1") (pin "2") (pinfunction "2_2") (pintype "passive"))
      (node (ref "U2") (pin "10") (pinfunction "IO8_10") (pintype "bidirectional"))
    )
    (net (code "15") (name "I2C_PW") (class "Default")
      (node (ref "C1") (pin "1") (pinfunction "1_1") (pintype "passive"))
      (node (ref "C2") (pin "1") (pinfunction "1_1") (pintype "passive"))
      (node (ref "R1_PINH") (pin "1") (pinfunction "1_1") (pintype "passive"))
      (node (ref "R2-PINH") (pin "1") (pinfunction "1_1") (pintype "passive"))
      (node (ref "U1") (pin "2") (pinfunction "CSB_2") (pintype "input"))
      (node (ref "U1") (pin "6") (pinfunction "VDDIO_6") (pintype "power_in"))
      (node (ref "U1") (pin "8") (pinfunction "VDD_8") (pintype "power_in"))
      (node (ref "U2") (pin "17") (pinfunction "IO19_17") (pintype "bidirectional"))
    )
    (net (code "16") (name "INT_RTC") (class "Default")
      (node (ref "R1_PINH1") (pin "2") (pinfunction "2_2") (pintype "passive"))
      (node (ref "TP15") (pin "TP") (pinfunction "TP_TP") (pintype "input"))
      (node (ref "U2") (pin "8") (pinfunction "IO0_8") (pintype "bidirectional"))
      (node (ref "U4") (pin "3") (pinfunction "SQW/~{INT}_3") (pintype "output"))
    )
    (net (code "17") (name "IO{slash}BOOT") (class "Default")
      (node (ref "BOOT_BUTTON") (pin "3") (pinfunction "3_3") (pintype "passive"))
      (node (ref "BOOT_BUTTON") (pin "4") (pinfunction "4_4") (pintype "passive"))
      (node (ref "C6") (pin "1") (pinfunction "1_1") (pintype "passive"))
      (node (ref "R_BOOT") (pin "2") (pinfunction "2_2") (pintype "passive"))
      (node (ref "U2") (pin "15") (pinfunction "IO9_15") (pintype "bidirectional"))
    )
    (net (code "18") (name "IO{slash}CHANGE") (class "Default")
      (node (ref "C10") (pin "1") (pinfunction "1_1") (pintype "passive"))
      (node (ref "CHANGE_BUTTON") (pin "3") (pinfunction "3_3") (pintype "passive"))
      (node (ref "CHANGE_BUTTON") (pin "4") (pinfunction "4_4") (pintype "passive"))
      (node (ref "R_CHANGE") (pin "2") (pinfunction "2_2") (pintype "passive"))
      (node (ref "U2") (pin "23") (pinfunction "IO15_23") (pintype "bidirectional"))
    )
    (net (code "19") (name "MISO") (class "Default")
      (node (ref "J2") (pin "P7") (pinfunction "DAT0_P7") (pintype "bidirectional"))
      (node (ref "TP6") (pin "TP") (pinfunction "TP_TP") (pintype "input"))
      (node (ref "U2") (pin "27") (pinfunction "IO2_27") (pintype "bidirectional"))
      (node (ref "U5") (pin "2") (pinfunction "DO(IO1)_2") (pintype "bidirectional"))
    )
    (net (code "20") (name "MOSI") (class "Default")
      (node (ref "J2") (pin "P3") (pinfunction "CMD_P3") (pintype "bidirectional"))
      (node (ref "J4") (pin "14") (pinfunction "14_14") (pintype "bidirectional"))
      (node (ref "TP7") (pin "TP") (pinfunction "TP_TP") (pintype "input"))
      (node (ref "U2") (pin "7") (pinfunction "IO7_7") (pintype "bidirectional"))
      (node (ref "U5") (pin "5") (pinfunction "DI(IO0)_5") (pintype "bidirectional"))
    )
    (net (code "21") (name "N$13") (class "Default")
      (node (ref "D12") (pin "2") (pinfunction "2_2") (pintype "passive"))
      (node (ref "R8") (pin "2") (pinfunction "2_2") (pintype "passive"))
    )
    (net (code "22") (name "N$14") (class "Default")
      (node (ref "D11") (pin "2") (pinfunction "2_2") (pintype "passive"))
      (node (ref "R7") (pin "2") (pinfunction "2_2") (pintype "passive"))
    )
    (net (code "23") (name "N$15") (class "Default")
      (node (ref "D10") (pin "2") (pinfunction "2_2") (pintype "passive"))
      (node (ref "R6") (pin "2") (pinfunction "2_2") (pintype "passive"))
    )
    (net (code "24") (name "N$16") (class "Default")
      (node (ref "D9") (pin "2") (pinfunction "2_2") (pintype "passive"))
      (node (ref "R5") (pin "2") (pinfunction "2_2") (pintype "passive"))
    )
    (net (code "25") (name "N$17") (class "Default")
      (node (ref "D6") (pin "2") (pinfunction "2_2") (pintype "passive"))
      (node (ref "R9") (pin "2") (pinfunction "2_2") (pintype "passive"))
    )
    (net (code "26") (name "N$18") (class "Default")
      (node (ref "D8") (pin "2") (pinfunction "2_2") (pintype "passive"))
      (node (ref "R10") (pin "2") (pinfunction "2_2") (pintype "passive"))
    )
    (net (code "27") (name "Net-(CHG_LED-PadC)") (class "Default")
      (node (ref "CHG_LED") (pin "C") (pinfunction "C_C") (pintype "passive"))
      (node (ref "R1_BAT") (pin "1") (pinfunction "1_1") (pintype "passive"))
    )
    (net (code "28") (name "Net-(D2-CATHODE)") (class "Default")
      (node (ref "C1_BAT1") (pin "1") (pinfunction "1_1") (pintype "passive"))
      (node (ref "D2") (pin "2") (pinfunction "CATHODE_2") (pintype "bidirectional"))
      (node (ref "IC1") (pin "1") (pinfunction "VIN_1") (pintype "bidirectional"))
      (node (ref "IC1") (pin "3") (pinfunction "CE_3") (pintype "bidirectional"))
      (node (ref "Q1") (pin "2") (pinfunction "S_2") (pintype "bidirectional"))
    )
    (net (code "29") (name "Net-(D3-A)") (class "Default")
      (node (ref "C4") (pin "1") (pinfunction "1_1") (pintype "passive"))
      (node (ref "D3") (pin "2") (pinfunction "A_2") (pintype "bidirectional"))
      (node (ref "D4") (pin "1") (pinfunction "K_1") (pintype "bidirectional"))
    )
    (net (code "30") (name "Net-(D7-CATHODE)") (class "Default")
      (node (ref "D7") (pin "2") (pinfunction "CATHODE_2") (pintype "bidirectional"))
      (node (ref "R_CAPACITOR") (pin "1") (pinfunction "1_1") (pintype "passive"))
    )
    (net (code "31") (name "Net-(EDP_C1-Pad2)") (class "Default")
      (node (ref "EDP_C1") (pin "2") (pinfunction "2_2") (pintype "passive"))
      (node (ref "J4") (pin "4") (pinfunction "4_4") (pintype "bidirectional"))
    )
    (net (code "32") (name "Net-(EDP_C2-Pad1)") (class "Default")
      (node (ref "EDP_C2") (pin "1") (pinfunction "1_1") (pintype "passive"))
      (node (ref "J4") (pin "5") (pinfunction "5_5") (pintype "bidirectional"))
    )
    (net (code "33") (name "Net-(EDP_C6-Pad1)") (class "Default")
      (node (ref "EDP_C6") (pin "1") (pinfunction "1_1") (pintype "passive"))
      (node (ref "J4") (pin "18") (pinfunction "18_18") (pintype "bidirectional"))
    )
    (net (code "34") (name "Net-(EDP_C7-Pad1)") (class "Default")
      (node (ref "EDP_C7") (pin "1") (pinfunction "1_1") (pintype "passive"))
      (node (ref "J4") (pin "19") (pinfunction "19_19") (pintype "bidirectional"))
    )
    (net (code "35") (name "Net-(EDP_C8-Pad1)") (class "Default")
      (node (ref "EDP_C8") (pin "1") (pinfunction "1_1") (pintype "passive"))
      (node (ref "J4") (pin "20") (pinfunction "20_20") (pintype "bidirectional"))
    )
    (net (code "36") (name "Net-(EDP_C10-Pad1)") (class "Default")
      (node (ref "EDP_C10") (pin "1") (pinfunction "1_1") (pintype "passive"))
      (node (ref "J4") (pin "22") (pinfunction "22_22") (pintype "bidirectional"))
    )
    (net (code "37") (name "Net-(EDP_C12-Pad1)") (class "Default")
      (node (ref "EDP_C12") (pin "1") (pinfunction "1_1") (pintype "passive"))
      (node (ref "J4") (pin "24") (pinfunction "24_24") (pintype "bidirectional"))
    )
    (net (code "38") (name "Net-(IC2-CT)") (class "Default")
      (node (ref "C_DELAY") (pin "1") (pinfunction "1_1") (pintype "passive"))
      (node (ref "IC2") (pin "5") (pinfunction "CT_5") (pintype "bidirectional"))
    )
    (net (code "39") (name "Net-(J1-PadA5)") (class "Default")
      (node (ref "J1") (pin "A5") (pinfunction "A5_A5") (pintype "bidirectional"))
      (node (ref "R2-USB1") (pin "2") (pinfunction "2_2") (pintype "passive"))
    )
    (net (code "40") (name "Net-(J1-PadB5)") (class "Default")
      (node (ref "J1") (pin "B5") (pinfunction "B5_B5") (pintype "bidirectional"))
      (node (ref "R2-USB") (pin "1") (pinfunction "1_1") (pintype "passive"))
    )
    (net (code "41") (name "Net-(U6-PROG)") (class "Default")
      (node (ref "R2_BAT") (pin "1") (pinfunction "1_1") (pintype "passive"))
      (node (ref "U6") (pin "5") (pinfunction "PROG_5") (pintype "input"))
    )
    (net (code "42") (name "Net-(U6-STAT)") (class "Default")
      (node (ref "R1_BAT") (pin "2") (pinfunction "2_2") (pintype "passive"))
      (node (ref "U6") (pin "1") (pinfunction "STAT_1") (pintype "output"))
    )
    (net (code "43") (name "PREVGH") (class "Default")
      (node (ref "D5") (pin "1") (pinfunction "K_1") (pintype "bidirectional"))
      (node (ref "EDP_C9") (pin "1") (pinfunction "1_1") (pintype "passive"))
      (node (ref "J4") (pin "21") (pinfunction "21_21") (pintype "bidirectional"))
    )
    (net (code "44") (name "PREVGL") (class "Default")
      (node (ref "D4") (pin "2") (pinfunction "A_2") (pintype "bidirectional"))
      (node (ref "EDP_C11") (pin "1") (pinfunction "1_1") (pintype "passive"))
      (node (ref "J4") (pin "23") (pinfunction "23_23") (pintype "bidirectional"))
    )
    (net (code "45") (name "RESE") (class "Default")
      (node (ref "J4") (pin "3") (pinfunction "3_3") (pintype "bidirectional"))
      (node (ref "Q2") (pin "2") (pinfunction "S_2") (pintype "bidirectional"))
      (node (ref "R3") (pin "2") (pinfunction "2_2") (pintype "passive"))
    )
    (net (code "46") (name "RESE'") (class "Default")
      (node (ref "R2") (pin "1") (pinfunction "1_1") (pintype "passive"))
      (node (ref "R3") (pin "1") (pinfunction "1_1") (pintype "passive"))
      (node (ref "SJ1") (pin "2") (pinfunction "2_2") (pintype "passive"))
    )
    (net (code "47") (name "RESET") (class "Default")
      (node (ref "C5") (pin "1") (pinfunction "1_1") (pintype "passive"))
      (node (ref "IC2") (pin "1") (pinfunction "VOUT_1") (pintype "bidirectional"))
      (node (ref "RESET_BUTTON") (pin "3") (pinfunction "3_3") (pintype "passive"))
      (node (ref "RESET_BUTTON") (pin "4") (pinfunction "4_4") (pintype "passive"))
      (node (ref "R_RESET") (pin "2") (pinfunction "2_2") (pintype "passive"))
      (node (ref "U2") (pin "3") (pinfunction "EN_3") (pintype "input"))
    )
    (net (code "48") (name "RTC_RST") (class "Default")
      (node (ref "U2") (pin "16") (pinfunction "IO18_16") (pintype "bidirectional"))
      (node (ref "U4") (pin "4") (pinfunction "~{RST}_4") (pintype "input"))
    )
    (net (code "49") (name "RX") (class "Default")
      (node (ref "TP2") (pin "TP") (pinfunction "TP_TP") (pintype "input"))
      (node (ref "U2") (pin "24") (pinfunction "RXD0/GPIO17_24") (pintype "bidirectional"))
    )
    (net (code "50") (name "SCK") (class "Default")
      (node (ref "J2") (pin "P5") (pinfunction "CLK_P5") (pintype "bidirectional"))
      (node (ref "J4") (pin "13") (pinfunction "13_13") (pintype "bidirectional"))
      (node (ref "TP8") (pin "TP") (pinfunction "TP_TP") (pintype "input"))
      (node (ref "U2") (pin "6") (pinfunction "IO6_6") (pintype "bidirectional"))
      (node (ref "U5") (pin "6") (pinfunction "CLK_6") (pintype "input"))
    )
    (net (code "51") (name "SCL") (class "Default")
      (node (ref "J3") (pin "4") (pinfunction "4_4") (pintype "passive"))
      (node (ref "R2-PINH") (pin "2") (pinfunction "2_2") (pintype "passive"))
      (node (ref "U1") (pin "4") (pinfunction "SCK_4") (pintype "input"))
      (node (ref "U2") (pin "20") (pinfunction "IO22_20") (pintype "bidirectional"))
      (node (ref "U3") (pin "7") (pinfunction "SCL_7") (pintype "input"))
      (node (ref "U4") (pin "16") (pinfunction "SCL_16") (pintype "input"))
    )
    (net (code "52") (name "SDA") (class "Default")
      (node (ref "J3") (pin "3") (pinfunction "3_3") (pintype "passive"))
      (node (ref "R1_PINH") (pin "2") (pinfunction "2_2") (pintype "passive"))
      (node (ref "U1") (pin "3") (pinfunction "SDI_3") (pintype "bidirectional"))
      (node (ref "U2") (pin "19") (pinfunction "IO21_19") (pintype "bidirectional"))
      (node (ref "U3") (pin "8") (pinfunction "SDA_8") (pintype "bidirectional"))
      (node (ref "U4") (pin "15") (pinfunction "SDA_15") (pintype "bidirectional"))
    )
    (net (code "53") (name "SRC") (class "Default")
      (node (ref "C4") (pin "2") (pinfunction "2_2") (pintype "passive"))
      (node (ref "D5") (pin "2") (pinfunction "A_2") (pintype "bidirectional"))
      (node (ref "L1") (pin "1") (pinfunction "1_1") (pintype "passive"))
      (node (ref "Q2") (pin "3") (pinfunction "D_3") (pintype "bidirectional"))
    )
    (net (code "54") (name "SS_SD") (class "Default")
      (node (ref "J2") (pin "P2") (pinfunction "CD/DAT3_P2") (pintype "bidirectional"))
      (node (ref "U2") (pin "4") (pinfunction "IO4_4") (pintype "bidirectional"))
    )
    (net (code "55") (name "TX") (class "Default")
      (node (ref "TP1") (pin "TP") (pinfunction "TP_TP") (pintype "input"))
      (node (ref "U2") (pin "25") (pinfunction "TXD0/GPIO16_25") (pintype "bidirectional"))
    )
    (net (code "56") (name "USB_D+") (class "Default")
      (node (ref "D1") (pin "1") (pinfunction "I/O1_1_1") (pintype "bidirectional"))
      (node (ref "U2") (pin "14") (pinfunction "IO13_14") (pintype "bidirectional"))
    )
    (net (code "57") (name "USB_D-") (class "Default")
      (node (ref "D1") (pin "3") (pinfunction "I/O2_1_3") (pintype "bidirectional"))
      (node (ref "U2") (pin "13") (pinfunction "IO12_13") (pintype "bidirectional"))
    )
    (net (code "58") (name "VBAT") (class "Default")
      (node (ref "C2_BAT") (pin "1") (pinfunction "1_1") (pintype "passive"))
      (node (ref "Q1") (pin "3") (pinfunction "D_3") (pintype "bidirectional"))
      (node (ref "TP3") (pin "TP") (pinfunction "TP_TP") (pintype "input"))
      (node (ref "U3") (pin "2") (pinfunction "CELL_2") (pintype "power_in"))
      (node (ref "U3") (pin "3") (pinfunction "VDD_3") (pintype "power_in"))
      (node (ref "U6") (pin "3") (pinfunction "VBAT_3") (pintype "power_in"))
    )
    (net (code "59") (name "VBUS") (class "Default")
      (node (ref "C1_BAT") (pin "1") (pinfunction "1_1") (pintype "passive"))
      (node (ref "C4_USB") (pin "1") (pinfunction "1_1") (pintype "passive"))
      (node (ref "C5_USB") (pin "1") (pinfunction "1_1") (pintype "passive"))
      (node (ref "CHG_LED") (pin "A") (pinfunction "A_A") (pintype "passive"))
      (node (ref "D1") (pin "5") (pinfunction "VBUS_5") (pintype "bidirectional"))
      (node (ref "D2") (pin "1") (pinfunction "ANODE_1") (pintype "bidirectional"))
      (node (ref "PFMF.050.1") (pin "2") (pinfunction "2_2") (pintype "passive"))
      (node (ref "Q1") (pin "1") (pinfunction "G_1") (pintype "bidirectional"))
      (node (ref "R1_PWRUSB") (pin "1") (pinfunction "1_1") (pintype "passive"))
      (node (ref "TP14") (pin "TP") (pinfunction "TP_TP") (pintype "input"))
      (node (ref "U6") (pin "4") (pinfunction "VIN_4") (pintype "power_in"))
    )
    (net (code "60") (name "VRTC") (class "Default")
      (node (ref "C10_SUPERCAP") (pin "1") (pinfunction "1_1") (pintype "passive"))
      (node (ref "C8") (pin "1") (pinfunction "1_1") (pintype "passive"))
      (node (ref "R_CAPACITOR") (pin "2") (pinfunction "2_2") (pintype "passive"))
      (node (ref "U4") (pin "14") (pinfunction "VBAT_14") (pintype "power_in"))
    )
    (net (code "61") (name "VUSB") (class "Default")
      (node (ref "J1") (pin "A4") (pinfunction "A4_A4") (pintype "bidirectional"))
      (node (ref "J1") (pin "A9") (pinfunction "A9_A9") (pintype "bidirectional"))
      (node (ref "J1") (pin "B4") (pinfunction "B4_B4") (pintype "bidirectional"))
      (node (ref "J1") (pin "B9") (pinfunction "B9_B9") (pintype "bidirectional"))
      (node (ref "PFMF.050.1") (pin "1") (pinfunction "1_1") (pintype "passive"))
    )
    (net (code "62") (name "unconnected-(IC1-NC-Pad4)") (class "Default")
      (node (ref "IC1") (pin "4") (pinfunction "NC_4") (pintype "no_connect"))
    )
    (net (code "63") (name "unconnected-(IC2-NC-Pad4)") (class "Default")
      (node (ref "IC2") (pin "4") (pinfunction "NC_4") (pintype "no_connect"))
    )
    (net (code "64") (name "unconnected-(J1-PadA8)") (class "Default")
      (node (ref "J1") (pin "A8") (pinfunction "A8_A8") (pintype "bidirectional"))
    )
    (net (code "65") (name "unconnected-(J1-PadB8)") (class "Default")
      (node (ref "J1") (pin "B8") (pinfunction "B8_B8") (pintype "bidirectional"))
    )
    (net (code "66") (name "unconnected-(J2-DAT1-PadP8)") (class "Default")
      (node (ref "J2") (pin "P8") (pinfunction "DAT1_P8") (pintype "bidirectional"))
    )
    (net (code "67") (name "unconnected-(J2-DAT2-PadP1)") (class "Default")
      (node (ref "J2") (pin "P1") (pinfunction "DAT2_P1") (pintype "bidirectional"))
    )
    (net (code "68") (name "unconnected-(J2-DETECTION_1-PadS1)") (class "Default")
      (node (ref "J2") (pin "S1") (pinfunction "DETECTION_1_S1") (pintype "bidirectional"))
    )
    (net (code "69") (name "unconnected-(J2-DETECTION_2-PadS2)") (class "Default")
      (node (ref "J2") (pin "S2") (pinfunction "DETECTION_2_S2") (pintype "bidirectional"))
    )
    (net (code "70") (name "unconnected-(J4-Pad1)") (class "Default")
      (node (ref "J4") (pin "1") (pinfunction "1_1") (pintype "bidirectional"))
    )
    (net (code "71") (name "unconnected-(J4-Pad6)") (class "Default")
      (node (ref "J4") (pin "6") (pinfunction "6_6") (pintype "bidirectional"))
    )
    (net (code "72") (name "unconnected-(J4-Pad7)") (class "Default")
      (node (ref "J4") (pin "7") (pinfunction "7_7") (pintype "bidirectional"))
    )
    (net (code "73") (name "unconnected-(U2-NC-Pad22)") (class "Default")
      (node (ref "U2") (pin "22") (pinfunction "NC_22") (pintype "no_connect"))
    )
    (net (code "74") (name "unconnected-(U3-~{ALERT}-Pad5)") (class "Default")
      (node (ref "U3") (pin "5") (pinfunction "~{ALERT}_5") (pintype "output"))
    )
  )
)
